# Qwiic_GPS_-_Titan_X1.net
KiCad netlist of a schematic drawn in EAGLE
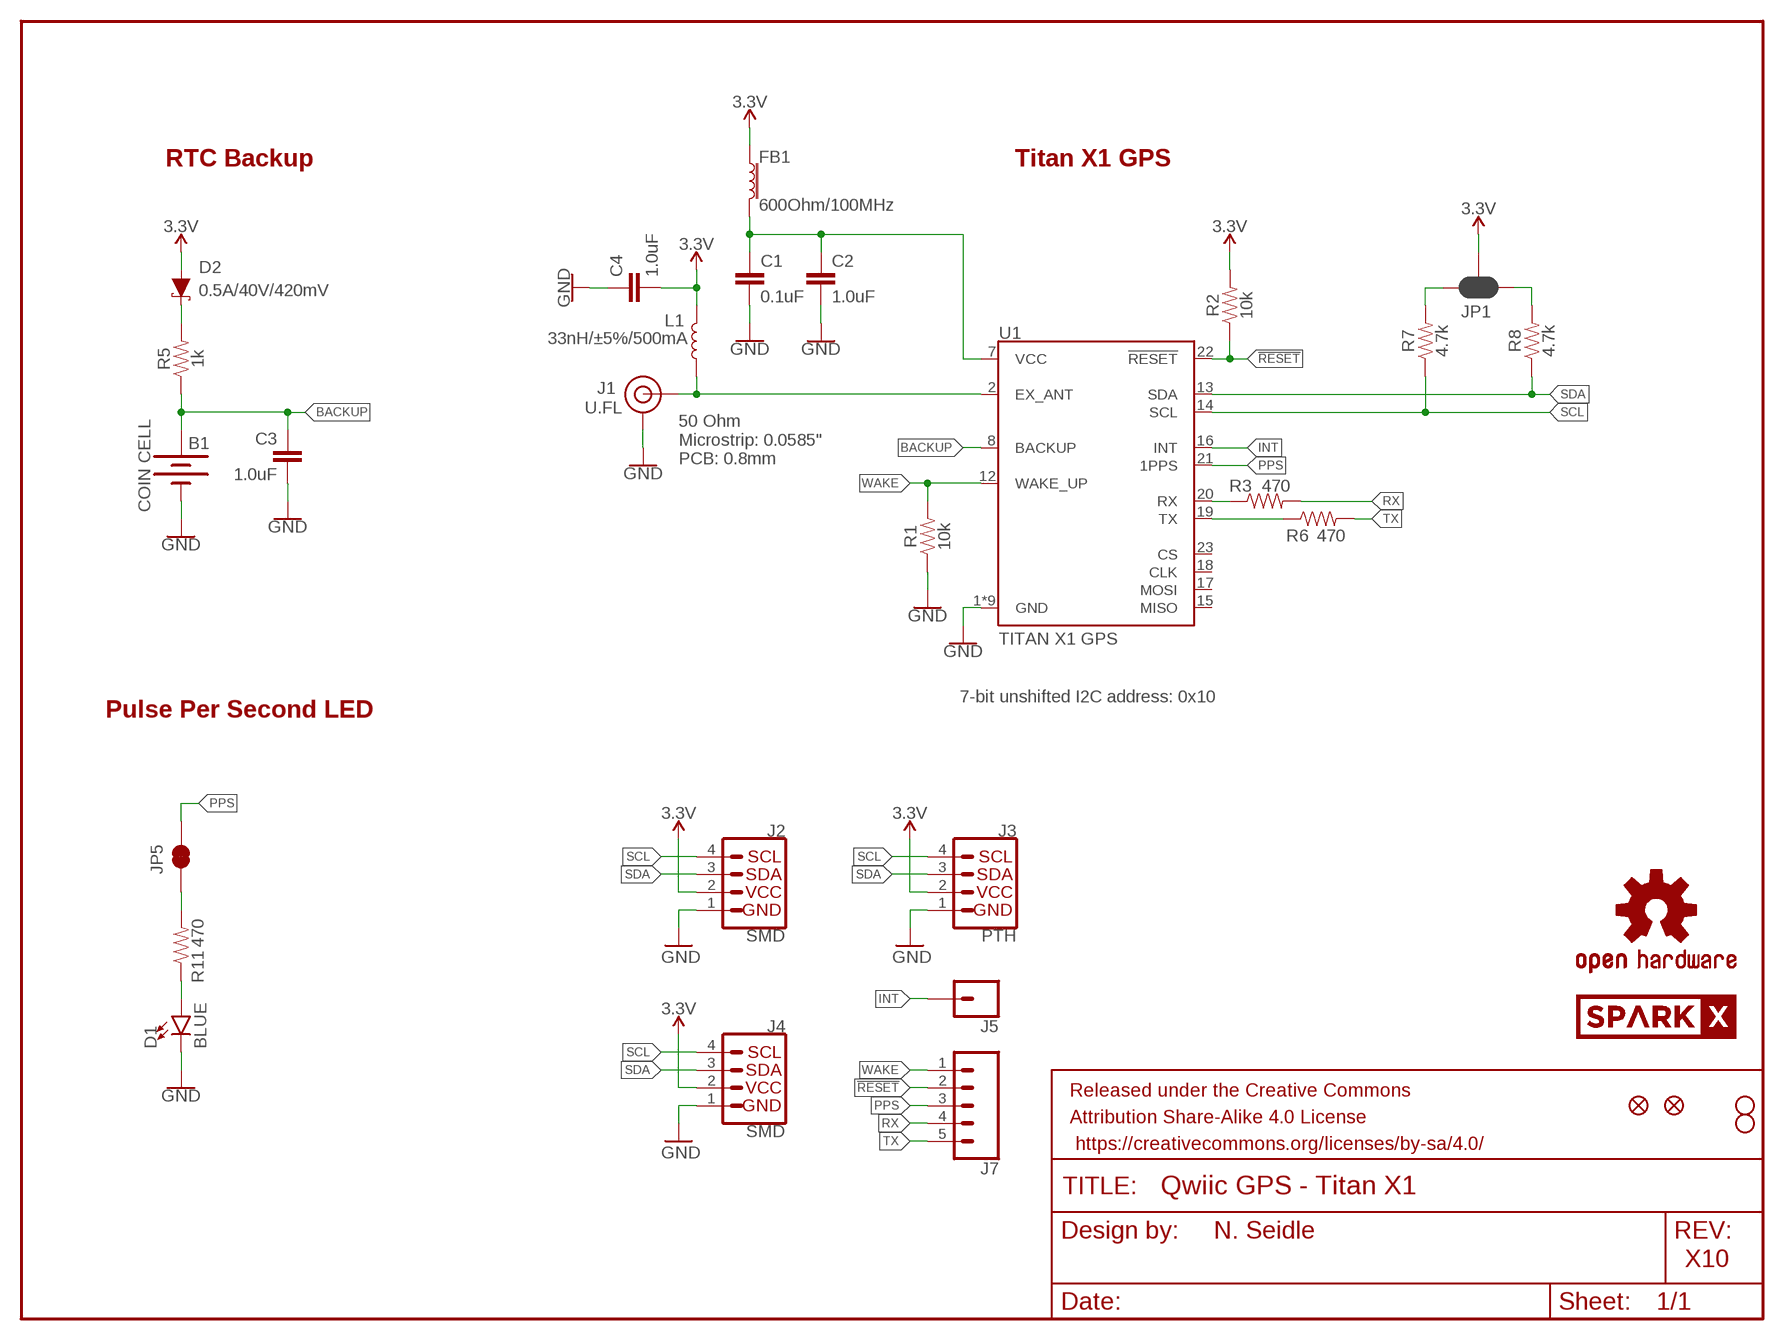
[diagram p0: schematic, sheet 1]

(export (version "E")
  (design (tool "Eeschema 10.0.6"))
  (components
    (comp (ref "B1")
      (value "COIN CELL")
      (footprint "eagle-import:6.8MM_COIN_CELL")
      (libsource (lib "eagle-import") (part "6.8MM_COIN_CELL"))
    )
    (comp (ref "C1")
      (value "0.1uF")
      (footprint "eagle-import:0603")
      (libsource (lib "eagle-import") (part "0.1UF-0603-25V-(+80/-20%)"))
    )
    (comp (ref "C2")
      (value "1.0uF")
      (footprint "eagle-import:0603")
      (libsource (lib "eagle-import") (part "1.0UF-0603-16V-10%"))
    )
    (comp (ref "C3")
      (value "1.0uF")
      (footprint "eagle-import:0603")
      (libsource (lib "eagle-import") (part "1.0UF-0603-16V-10%"))
    )
    (comp (ref "C4")
      (value "1.0uF")
      (footprint "eagle-import:0603")
      (libsource (lib "eagle-import") (part "1.0UF-0603-16V-10%"))
    )
    (comp (ref "D1")
      (value "BLUE")
      (footprint "eagle-import:LED-0603")
      (libsource (lib "eagle-import") (part "LED-BLUE0603"))
    )
    (comp (ref "D2")
      (value "0.5A/40V/420mV")
      (footprint "eagle-import:SOD-323")
      (libsource (lib "eagle-import") (part "DIODE-SCHOTTKY-PMEG4005EJ"))
    )
    (comp (ref "FB1")
      (value "600Ohm/100MHz")
      (footprint "eagle-import:0603")
      (libsource (lib "eagle-import") (part "FERRITE_BEAD-0603"))
    )
    (comp (ref "FRAME1")
      (value "FRAME-LETTER")
      (footprint "eagle-import:CREATIVE_COMMONS")
      (libsource (lib "eagle-import") (part "FRAME-LETTER"))
    )
    (comp (ref "J1")
      (value "U.FL")
      (footprint "eagle-import:U.FL")
      (libsource (lib "eagle-import") (part "U.FL"))
    )
    (comp (ref "J2")
      (value "SMD")
      (footprint "eagle-import:1X04_1MM_RA")
      (libsource (lib "eagle-import") (part "I2C_STANDARDJS-1MM"))
    )
    (comp (ref "J3")
      (value "PTH")
      (footprint "eagle-import:1X04_NO_SILK")
      (libsource (lib "eagle-import") (part "I2C_STANDARD_NO_SILK"))
    )
    (comp (ref "J4")
      (value "SMD")
      (footprint "eagle-import:1X04_1MM_RA")
      (libsource (lib "eagle-import") (part "I2C_STANDARDJS-1MM"))
    )
    (comp (ref "J5")
      (value "CONN_01PTH_NO_SILK_YES_STOP")
      (footprint "eagle-import:1X01_NO_SILK")
      (libsource (lib "eagle-import") (part "CONN_01PTH_NO_SILK_YES_STOP"))
    )
    (comp (ref "J7")
      (value "CONN_05NO_SILK")
      (footprint "eagle-import:1X05_NO_SILK")
      (libsource (lib "eagle-import") (part "CONN_05NO_SILK"))
    )
    (comp (ref "JP1")
      (value "JUMPER-SMT_3_2-NC_PASTE_SILK")
      (footprint "eagle-import:SMT-JUMPER_3_2-NC_PASTE_SILK")
      (libsource (lib "eagle-import") (part "JUMPER-SMT_3_2-NC_PASTE_SILK"))
    )
    (comp (ref "JP2")
      (value "FIDUCIALUFIDUCIAL")
      (footprint "eagle-import:MICRO-FIDUCIAL")
      (libsource (lib "eagle-import") (part "FIDUCIALUFIDUCIAL"))
    )
    (comp (ref "JP3")
      (value "STAND-OFF")
      (footprint "eagle-import:STAND-OFF")
      (libsource (lib "eagle-import") (part "STAND-OFF"))
    )
    (comp (ref "JP4")
      (value "STAND-OFF")
      (footprint "eagle-import:STAND-OFF")
      (libsource (lib "eagle-import") (part "STAND-OFF"))
    )
    (comp (ref "JP5")
      (value "JUMPER-SMT_2_NC_TRACE_NO-SILK")
      (footprint "eagle-import:SMT-JUMPER_2_NC_TRACE_NO-SILK")
      (libsource (lib "eagle-import") (part "JUMPER-SMT_2_NC_TRACE_NO-SILK"))
    )
    (comp (ref "JP6")
      (value "FIDUCIALUFIDUCIAL")
      (footprint "eagle-import:MICRO-FIDUCIAL")
      (libsource (lib "eagle-import") (part "FIDUCIALUFIDUCIAL"))
    )
    (comp (ref "L1")
      (value "33nH/±5%/500mA")
      (footprint "eagle-import:0603")
      (libsource (lib "eagle-import") (part "INDUCTOR-0603-33NH"))
    )
    (comp (ref "LOGO1")
      (value "OSHW-LOGOMINI")
      (footprint "eagle-import:OSHW-LOGO-MINI")
      (libsource (lib "eagle-import") (part "OSHW-LOGOMINI"))
    )
    (comp (ref "R1")
      (value "10k")
      (footprint "eagle-import:0603")
      (libsource (lib "eagle-import") (part "10KOHM-0603-1/10W-1%"))
    )
    (comp (ref "R2")
      (value "10k")
      (footprint "eagle-import:0603")
      (libsource (lib "eagle-import") (part "10KOHM-0603-1/10W-1%"))
    )
    (comp (ref "R3")
      (value "470")
      (footprint "eagle-import:0603")
      (libsource (lib "eagle-import") (part "470OHM-0603-1/10W-1%"))
    )
    (comp (ref "R5")
      (value "1k")
      (footprint "eagle-import:0603")
      (libsource (lib "eagle-import") (part "1KOHM-0603-1/10W-1%"))
    )
    (comp (ref "R6")
      (value "470")
      (footprint "eagle-import:0603")
      (libsource (lib "eagle-import") (part "470OHM-0603-1/10W-1%"))
    )
    (comp (ref "R7")
      (value "4.7k")
      (footprint "eagle-import:0603")
      (libsource (lib "eagle-import") (part "4.7KOHM-0603-1/10W-1%"))
    )
    (comp (ref "R8")
      (value "4.7k")
      (footprint "eagle-import:0603")
      (libsource (lib "eagle-import") (part "4.7KOHM-0603-1/10W-1%"))
    )
    (comp (ref "R11")
      (value "470")
      (footprint "eagle-import:0603")
      (libsource (lib "eagle-import") (part "470OHM-0603-1/10W-1%"))
    )
    (comp (ref "U$1")
      (value "SPARKX-LOGO5")
      (footprint "eagle-import:SPARKX-LARGE")
      (libsource (lib "eagle-import") (part "SPARKX-LOGO5"))
    )
    (comp (ref "U1")
      (value "TITAN X1 GPS")
      (footprint "eagle-import:TITAN_X1_GPS")
      (libsource (lib "eagle-import") (part "TITAN_X1_GPS"))
    )
  )
  (nets
    (net (code "1") (name "/~{RESET}") (class "Default")
      (node (ref "J7") (pin "2") (pinfunction "2_2") (pintype "passive"))
      (node (ref "R2") (pin "1") (pinfunction "1_1") (pintype "passive"))
      (node (ref "U1") (pin "22") (pinfunction "~{RESET}_22") (pintype "bidirectional"))
    )
    (net (code "2") (name "3.3V") (class "Default")
      (node (ref "C4") (pin "2") (pinfunction "2_2") (pintype "passive"))
      (node (ref "D2") (pin "A") (pinfunction "A_A") (pintype "passive"))
      (node (ref "FB1") (pin "1") (pinfunction "1_1") (pintype "passive"))
      (node (ref "J2") (pin "2") (pinfunction "VCC_2") (pintype "power_in"))
      (node (ref "J3") (pin "2") (pinfunction "VCC_2") (pintype "power_in"))
      (node (ref "J4") (pin "2") (pinfunction "VCC_2") (pintype "power_in"))
      (node (ref "JP1") (pin "2") (pinfunction "2_2") (pintype "passive"))
      (node (ref "L1") (pin "2") (pinfunction "2_2") (pintype "passive"))
      (node (ref "R2") (pin "2") (pinfunction "2_2") (pintype "passive"))
    )
    (net (code "3") (name "BACKUP") (class "Default")
      (node (ref "B1") (pin "+") (pinfunction "+_+") (pintype "power_in"))
      (node (ref "C3") (pin "1") (pinfunction "1_1") (pintype "passive"))
      (node (ref "R5") (pin "1") (pinfunction "1_1") (pintype "passive"))
      (node (ref "U1") (pin "8") (pinfunction "BACKUP_8") (pintype "bidirectional"))
    )
    (net (code "4") (name "GND") (class "Default")
      (node (ref "B1") (pin "-") (pinfunction "-_-") (pintype "power_in"))
      (node (ref "C1") (pin "2") (pinfunction "2_2") (pintype "passive"))
      (node (ref "C2") (pin "2") (pinfunction "2_2") (pintype "passive"))
      (node (ref "C3") (pin "2") (pinfunction "2_2") (pintype "passive"))
      (node (ref "C4") (pin "1") (pinfunction "1_1") (pintype "passive"))
      (node (ref "D1") (pin "C") (pinfunction "C_C") (pintype "passive"))
      (node (ref "J1") (pin "1") (pinfunction "GND_1") (pintype "bidirectional"))
      (node (ref "J1") (pin "2") (pinfunction "GND_2") (pintype "bidirectional"))
      (node (ref "J2") (pin "1") (pinfunction "GND_1") (pintype "power_in"))
      (node (ref "J3") (pin "1") (pinfunction "GND_1") (pintype "power_in"))
      (node (ref "J4") (pin "1") (pinfunction "GND_1") (pintype "power_in"))
      (node (ref "R1") (pin "1") (pinfunction "1_1") (pintype "passive"))
      (node (ref "U1") (pin "1") (pinfunction "GND_1") (pintype "bidirectional"))
      (node (ref "U1") (pin "10") (pinfunction "GND_10") (pintype "bidirectional"))
      (node (ref "U1") (pin "11") (pinfunction "GND_11") (pintype "bidirectional"))
      (node (ref "U1") (pin "24") (pinfunction "GND_24") (pintype "bidirectional"))
      (node (ref "U1") (pin "3") (pinfunction "GND_3") (pintype "bidirectional"))
      (node (ref "U1") (pin "4") (pinfunction "GND_4") (pintype "bidirectional"))
      (node (ref "U1") (pin "5") (pinfunction "GND_5") (pintype "bidirectional"))
      (node (ref "U1") (pin "6") (pinfunction "GND_6") (pintype "bidirectional"))
      (node (ref "U1") (pin "9") (pinfunction "GND_9") (pintype "bidirectional"))
    )
    (net (code "5") (name "INT") (class "Default")
      (node (ref "J5") (pin "1") (pinfunction "1_1") (pintype "passive"))
      (node (ref "U1") (pin "16") (pinfunction "INT_16") (pintype "bidirectional"))
    )
    (net (code "6") (name "Net-(D1-PadA)") (class "Default")
      (node (ref "D1") (pin "A") (pinfunction "A_A") (pintype "passive"))
      (node (ref "R11") (pin "1") (pinfunction "1_1") (pintype "passive"))
    )
    (net (code "7") (name "Net-(D2-PadC)") (class "Default")
      (node (ref "D2") (pin "C") (pinfunction "C_C") (pintype "passive"))
      (node (ref "R5") (pin "2") (pinfunction "2_2") (pintype "passive"))
    )
    (net (code "8") (name "Net-(J1-SIGNAL)") (class "Default")
      (node (ref "J1") (pin "FEED") (pinfunction "SIGNAL_FEED") (pintype "bidirectional"))
      (node (ref "L1") (pin "1") (pinfunction "1_1") (pintype "passive"))
      (node (ref "U1") (pin "2") (pinfunction "EX_ANT_2") (pintype "bidirectional"))
    )
    (net (code "9") (name "Net-(JP1-Pad1)") (class "Default")
      (node (ref "JP1") (pin "1") (pinfunction "1_1") (pintype "passive"))
      (node (ref "R8") (pin "2") (pinfunction "2_2") (pintype "passive"))
    )
    (net (code "10") (name "Net-(JP1-Pad3)") (class "Default")
      (node (ref "JP1") (pin "3") (pinfunction "3_3") (pintype "passive"))
      (node (ref "R7") (pin "2") (pinfunction "2_2") (pintype "passive"))
    )
    (net (code "11") (name "Net-(JP5-Pad1)") (class "Default")
      (node (ref "JP5") (pin "1") (pinfunction "1_1") (pintype "passive"))
      (node (ref "R11") (pin "2") (pinfunction "2_2") (pintype "passive"))
    )
    (net (code "12") (name "Net-(U1-RX)") (class "Default")
      (node (ref "R3") (pin "1") (pinfunction "1_1") (pintype "passive"))
      (node (ref "U1") (pin "20") (pinfunction "RX_20") (pintype "bidirectional"))
    )
    (net (code "13") (name "Net-(U1-TX)") (class "Default")
      (node (ref "R6") (pin "1") (pinfunction "1_1") (pintype "passive"))
      (node (ref "U1") (pin "19") (pinfunction "TX_19") (pintype "bidirectional"))
    )
    (net (code "14") (name "Net-(U1-VCC)") (class "Default")
      (node (ref "C1") (pin "1") (pinfunction "1_1") (pintype "passive"))
      (node (ref "C2") (pin "1") (pinfunction "1_1") (pintype "passive"))
      (node (ref "FB1") (pin "2") (pinfunction "2_2") (pintype "passive"))
      (node (ref "U1") (pin "7") (pinfunction "VCC_7") (pintype "bidirectional"))
    )
    (net (code "15") (name "PPS") (class "Default")
      (node (ref "J7") (pin "3") (pinfunction "3_3") (pintype "passive"))
      (node (ref "JP5") (pin "2") (pinfunction "2_2") (pintype "passive"))
      (node (ref "U1") (pin "21") (pinfunction "1PPS_21") (pintype "bidirectional"))
    )
    (net (code "16") (name "RX") (class "Default")
      (node (ref "J7") (pin "4") (pinfunction "4_4") (pintype "passive"))
      (node (ref "R3") (pin "2") (pinfunction "2_2") (pintype "passive"))
    )
    (net (code "17") (name "SCL") (class "Default")
      (node (ref "J2") (pin "4") (pinfunction "SCL_4") (pintype "passive"))
      (node (ref "J3") (pin "4") (pinfunction "SCL_4") (pintype "passive"))
      (node (ref "J4") (pin "4") (pinfunction "SCL_4") (pintype "passive"))
      (node (ref "R7") (pin "1") (pinfunction "1_1") (pintype "passive"))
      (node (ref "U1") (pin "14") (pinfunction "SCL_14") (pintype "bidirectional"))
    )
    (net (code "18") (name "SDA") (class "Default")
      (node (ref "J2") (pin "3") (pinfunction "SDA_3") (pintype "passive"))
      (node (ref "J3") (pin "3") (pinfunction "SDA_3") (pintype "passive"))
      (node (ref "J4") (pin "3") (pinfunction "SDA_3") (pintype "passive"))
      (node (ref "R8") (pin "1") (pinfunction "1_1") (pintype "passive"))
      (node (ref "U1") (pin "13") (pinfunction "SDA_13") (pintype "bidirectional"))
    )
    (net (code "19") (name "TX") (class "Default")
      (node (ref "J7") (pin "5") (pinfunction "5_5") (pintype "passive"))
      (node (ref "R6") (pin "2") (pinfunction "2_2") (pintype "passive"))
    )
    (net (code "20") (name "WAKE") (class "Default")
      (node (ref "J7") (pin "1") (pinfunction "1_1") (pintype "passive"))
      (node (ref "R1") (pin "2") (pinfunction "2_2") (pintype "passive"))
      (node (ref "U1") (pin "12") (pinfunction "WAKE_UP_12") (pintype "bidirectional"))
    )
    (net (code "21") (name "unconnected-(U1-CLK-Pad18)") (class "Default")
      (node (ref "U1") (pin "18") (pinfunction "CLK_18") (pintype "bidirectional"))
    )
    (net (code "22") (name "unconnected-(U1-CS-Pad23)") (class "Default")
      (node (ref "U1") (pin "23") (pinfunction "CS_23") (pintype "bidirectional"))
    )
    (net (code "23") (name "unconnected-(U1-MISO-Pad15)") (class "Default")
      (node (ref "U1") (pin "15") (pinfunction "MISO_15") (pintype "bidirectional"))
    )
    (net (code "24") (name "unconnected-(U1-MOSI-Pad17)") (class "Default")
      (node (ref "U1") (pin "17") (pinfunction "MOSI_17") (pintype "bidirectional"))
    )
  )
)
